# ESP_Grow_Main_Rev_A_2_3V_5V.net
KiCad netlist of a schematic drawn in Altium Designer
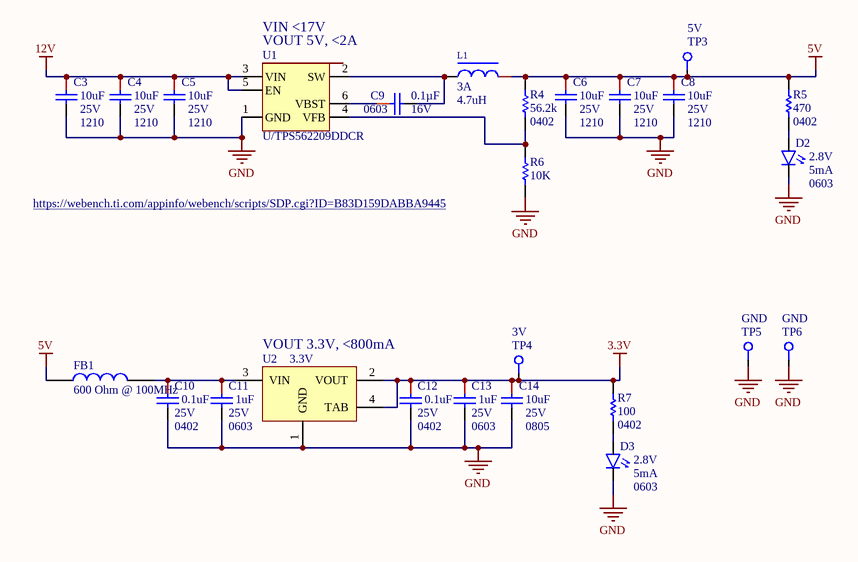
[diagram p0: ESP_Grow_Main_Rev_A_2_3V_5V.SchDoc]

(export (version "E")
  (design (tool "Eeschema 10.0.6"))
  (components
    (comp (ref "C3")
      (value "10uF")
      (footprint "CAPC1210(3225)_N")
      (description "10uF 1210 25V")
      (fields
        (field (name "MANUFACTURER") "TDK Corporation")
        (field (name "MANUFACTURER PART NUMBER") "C3225JB1E106K250AA")
        (field (name "PACKAGE / CASE") "1210")
        (field (name "VOLTAGE RATED") "25V")
      )
      (libsource (lib "OLogic-Passive") (part "CAP CER 10UF 25V JB 1210"))
    )
    (comp (ref "C4")
      (value "10uF")
      (footprint "CAPC1210(3225)_N")
      (description "10uF 1210 25V")
      (fields
        (field (name "MANUFACTURER") "TDK Corporation")
        (field (name "MANUFACTURER PART NUMBER") "C3225JB1E106K250AA")
        (field (name "PACKAGE / CASE") "1210")
        (field (name "VOLTAGE RATED") "25V")
      )
      (libsource (lib "OLogic-Passive") (part "CAP CER 10UF 25V JB 1210"))
    )
    (comp (ref "C5")
      (value "10uF")
      (footprint "CAPC1210(3225)_N")
      (description "10uF 1210 25V")
      (fields
        (field (name "MANUFACTURER") "TDK Corporation")
        (field (name "MANUFACTURER PART NUMBER") "C3225JB1E106K250AA")
        (field (name "PACKAGE / CASE") "1210")
        (field (name "VOLTAGE RATED") "25V")
      )
      (libsource (lib "OLogic-Passive") (part "CAP CER 10UF 25V JB 1210"))
    )
    (comp (ref "C6")
      (value "10uF")
      (footprint "CAPC1210(3225)_N")
      (description "10uF 1210 25V")
      (fields
        (field (name "MANUFACTURER") "TDK Corporation")
        (field (name "MANUFACTURER PART NUMBER") "C3225JB1E106K250AA")
        (field (name "PACKAGE / CASE") "1210")
        (field (name "VOLTAGE RATED") "25V")
      )
      (libsource (lib "OLogic-Passive") (part "CAP CER 10UF 25V JB 1210"))
    )
    (comp (ref "C7")
      (value "10uF")
      (footprint "CAPC1210(3225)_N")
      (description "10uF 1210 25V")
      (fields
        (field (name "MANUFACTURER") "TDK Corporation")
        (field (name "MANUFACTURER PART NUMBER") "C3225JB1E106K250AA")
        (field (name "PACKAGE / CASE") "1210")
        (field (name "VOLTAGE RATED") "25V")
      )
      (libsource (lib "OLogic-Passive") (part "CAP CER 10UF 25V JB 1210"))
    )
    (comp (ref "C8")
      (value "10uF")
      (footprint "CAPC1210(3225)_N")
      (description "10uF 1210 25V")
      (fields
        (field (name "MANUFACTURER") "TDK Corporation")
        (field (name "MANUFACTURER PART NUMBER") "C3225JB1E106K250AA")
        (field (name "PACKAGE / CASE") "1210")
        (field (name "VOLTAGE RATED") "25V")
      )
      (libsource (lib "OLogic-Passive") (part "CAP CER 10UF 25V JB 1210"))
    )
    (comp (ref "C9")
      (value "0.1uF")
      (footprint "CAPC0603(1608)_L")
      (description "0.1uF 0603 16V")
      (fields
        (field (name "MANUFACTURER") "Kemet")
        (field (name "MANUFACTURER PART NUMBER") "C0603C104K4RACTU")
        (field (name "CAPACITANCE") "0.1µF")
        (field (name "PACKAGE / CASE") "0603")
        (field (name "VOLTAGE - RATED") "16V")
      )
      (libsource (lib "OLogic-Passive") (part "CAP CER 0.1UF 16V 10% X7R 0603"))
    )
    (comp (ref "C10")
      (value "0.1uF")
      (footprint "CAPC0402(1005)_N")
      (description "0.1uF 0402 25V")
      (fields
        (field (name "MANUFACTURER") "Taiyo Yuden")
        (field (name "MANUFACTURER PART NUMBER") "TMK105BJ104KV-F")
        (field (name "PACKAGE / CASE") "0402")
        (field (name "VOLTAGE - RATED") "25V")
      )
      (libsource (lib "OLogic-Passive") (part "CAP CER 0.1UF 25V 10% X5R 0402"))
    )
    (comp (ref "C11")
      (value "1uF")
      (footprint "CAPC0603(1608)_N")
      (description "1uF 0603 25V")
      (fields
        (field (name "MANUFACTURER") "TDK Corporation")
        (field (name "MANUFACTURER PART NUMBER") "CGA3E1X7R1E105K080AC")
        (field (name "VOLTAGE - RATED") "25V")
        (field (name "PACKAGE / CASE") "0603")
      )
      (libsource (lib "OLogic-Passive") (part "CAP CER 1UF 25V 10% X7R 0603"))
    )
    (comp (ref "C12")
      (value "0.1uF")
      (footprint "CAPC0402(1005)_N")
      (description "0.1uF 0402 25V")
      (fields
        (field (name "MANUFACTURER") "Taiyo Yuden")
        (field (name "MANUFACTURER PART NUMBER") "TMK105BJ104KV-F")
        (field (name "PACKAGE / CASE") "0402")
        (field (name "VOLTAGE - RATED") "25V")
      )
      (libsource (lib "OLogic-Passive") (part "CAP CER 0.1UF 25V 10% X5R 0402"))
    )
    (comp (ref "C13")
      (value "1uF")
      (footprint "CAPC0603(1608)_N")
      (description "1uF 0603 25V")
      (fields
        (field (name "MANUFACTURER") "TDK Corporation")
        (field (name "MANUFACTURER PART NUMBER") "CGA3E1X7R1E105K080AC")
        (field (name "VOLTAGE - RATED") "25V")
        (field (name "PACKAGE / CASE") "0603")
      )
      (libsource (lib "OLogic-Passive") (part "CAP CER 1UF 25V 10% X7R 0603"))
    )
    (comp (ref "C14")
      (value "10uF")
      (footprint "CAPC0805(2012)_L")
      (description "10UF 25V X6R 0805")
      (fields
        (field (name "MANUFACTURER") "Murata Electronics North America")
        (field (name "MANUFACTURER PART NUMBER") "GRM21BC81E106ME51L")
        (field (name "VOLTAGE - RATED") "25V")
        (field (name "PACKAGE / CASE") "0805")
      )
      (libsource (lib "OLogic-Passive") (part "CAP CER 10UF 25V X6S 0805"))
    )
    (comp (ref "D2")
      (value "D/LEDB/0603")
      (footprint "D/0603")
      (fields
        (field (name "PACKAGE / CASE") "0603")
        (field (name "CURRENT - TEST") "5mA")
        (field (name "VOLTAGE - FORWARD (VF) (TYP)") "2.8V")
      )
      (libsource (lib "Kyle_Lib_04-20-19") (part "D/LEDB/0603"))
    )
    (comp (ref "D3")
      (value "D/LEDB/0603")
      (footprint "D/0603")
      (fields
        (field (name "PACKAGE / CASE") "0603")
        (field (name "CURRENT - TEST") "5mA")
        (field (name "VOLTAGE - FORWARD (VF) (TYP)") "2.8V")
      )
      (libsource (lib "Kyle_Lib_04-20-19") (part "D/LEDB/0603"))
    )
    (comp (ref "FB1")
      (value "600 Ohm @ 100MHz")
      (footprint "RESC0805(2012)_N")
      (description "600 OHM 0805 2.0A")
      (fields
        (field (name "MANUFACTURER") "Wurth Electronics Inc")
        (field (name "MANUFACTURER PART NUMBER") "742792040")
        (field (name "CREATOR") "osman")
      )
      (libsource (lib "OLogic-Passive") (part "FERRITE 600 OHM 2.0A 0805"))
    )
    (comp (ref "L1")
      (value "4.7uH")
      (footprint "INDP6060X45N")
      (description "FIXED IND 4.7UH 3A 37.6 MOHM SMD")
      (fields
        (field (name "MANUFACTURER PART NUMBER") "SRN6045-4R7Y")
        (field (name "CURRENT RATING (AMPS)") "3A")
        (field (name "INDUCTANCE") "4.7uH")
      )
      (libsource (lib "Kyle_Lib_04-20-19") (part "L/4.7uH/3A"))
    )
    (comp (ref "R4")
      (value "56.2K 1%")
      (footprint "RESC0402(1005)_N")
      (description "56.2K 1% 0402")
      (fields
        (field (name "MANUFACTURER") "Panasonic Electronic Components")
        (field (name "MANUFACTURER PART NUMBER") "ERJ-2RKF5622X")
        (field (name "RESISTANCE (OHMS)") "56.2k")
        (field (name "PACKAGE / CASE") "0402")
      )
      (libsource (lib "OLogic-Passive") (part "RES 56.2K OHM 1% 1/10W 0402"))
    )
    (comp (ref "R5")
      (value "470")
      (footprint "RESC0402(1005)_N")
      (description "470 0402")
      (fields
        (field (name "MANUFACTURER") "Panasonic Electronic Components")
        (field (name "MANUFACTURER PART NUMBER") "ERJ-2RKF4700X")
        (field (name "RESISTANCE (OHMS)") "470")
        (field (name "PACKAGE / CASE") "0402")
      )
      (libsource (lib "OLogic-Passive") (part "RES 470 OHM 1% 1/10W 0402"))
    )
    (comp (ref "R6")
      (value "10K")
      (footprint "RESC0402(1005)_N")
      (description "10K 0402")
      (fields
        (field (name "MANUFACTURER") "Samsung Electro-Mechanics")
        (field (name "MANUFACTURER PART NUMBER") "RC1005F103CS")
      )
      (libsource (lib "OLogic-Passive") (part "RES 10K OHM 1% 1/16W 0402"))
    )
    (comp (ref "R7")
      (value "100")
      (footprint "RESC0402(1005)_N")
      (description "100 0402")
      (fields
        (field (name "MANUFACTURER") "Yageo")
        (field (name "MANUFACTURER PART NUMBER") "RC0402FR-07100RL")
        (field (name "SUPPLIER DEVICE PACKAGE") "0402")
      )
      (libsource (lib "OLogic-Passive") (part "RES 100 OHM 1% 1/16W 0402"))
    )
    (comp (ref "TP3")
      (value "5V")
      (footprint "Pogo-Testpoint")
      (description "Test Point- Current one")
      (libsource (lib "OLogic Nexus Vault") (part "TestPoint"))
    )
    (comp (ref "TP4")
      (value "3V")
      (footprint "Pogo-Testpoint")
      (description "Test Point- Current one")
      (libsource (lib "OLogic Nexus Vault") (part "TestPoint"))
    )
    (comp (ref "TP5")
      (value "GND")
      (footprint "Pogo-Testpoint")
      (description "Test Point- Current one")
      (libsource (lib "OLogic Nexus Vault") (part "TestPoint"))
    )
    (comp (ref "TP6")
      (value "GND")
      (footprint "Pogo-Testpoint")
      (description "Test Point- Current one")
      (libsource (lib "OLogic Nexus Vault") (part "TestPoint"))
    )
    (comp (ref "U1")
      (value "U/TPS562209DDCR")
      (footprint "SOT-23")
      (description "IC REG BUCK ADJ 2A TSOT23-6")
      (fields (field (name "MANUFACTURER PART NUMBER") "TPS562209DDCR"))
      (libsource (lib "Kyle_Lib_04-20-19") (part "U/TPS562209DDCR"))
    )
    (comp (ref "U2")
      (value "3.3V")
      (footprint "DSO-G3")
      (description "3.3 volt fixed regulator, 800mA")
      (libsource (lib "OLogic-Reg-Convert") (part "LD1117S33"))
    )
  )
  (nets
    (net (code "1") (name "3.3V") (class "Default")
      (node (ref "C12") (pin "1") (pinfunction "1_1") (pintype "passive"))
      (node (ref "C13") (pin "1") (pinfunction "1_1") (pintype "passive"))
      (node (ref "C14") (pin "1") (pinfunction "1_1") (pintype "passive"))
      (node (ref "R7") (pin "2") (pinfunction "2_2") (pintype "passive"))
      (node (ref "TP4") (pin "1") (pinfunction "1_1") (pintype "passive"))
      (node (ref "U2") (pin "2") (pinfunction "VOUT_2") (pintype "power_in"))
      (node (ref "U2") (pin "4") (pinfunction "TAB_4") (pintype "power_in"))
    )
    (net (code "2") (name "5V") (class "Default")
      (node (ref "C6") (pin "1") (pinfunction "1_1") (pintype "passive"))
      (node (ref "C7") (pin "1") (pinfunction "1_1") (pintype "passive"))
      (node (ref "C8") (pin "1") (pinfunction "1_1") (pintype "passive"))
      (node (ref "FB1") (pin "1") (pinfunction "1_1") (pintype "passive"))
      (node (ref "L1") (pin "1") (pinfunction "1_1") (pintype "power_in"))
      (node (ref "R4") (pin "2") (pinfunction "2_2") (pintype "passive"))
      (node (ref "R5") (pin "2") (pinfunction "2_2") (pintype "passive"))
      (node (ref "TP3") (pin "1") (pinfunction "1_1") (pintype "passive"))
    )
    (net (code "3") (name "12V") (class "Default")
      (node (ref "C3") (pin "1") (pinfunction "1_1") (pintype "passive"))
      (node (ref "C4") (pin "1") (pinfunction "1_1") (pintype "passive"))
      (node (ref "C5") (pin "1") (pinfunction "1_1") (pintype "passive"))
      (node (ref "U1") (pin "3") (pinfunction "VIN_3") (pintype "power_in"))
      (node (ref "U1") (pin "5") (pinfunction "EN_5") (pintype "power_in"))
    )
    (net (code "4") (name "GND") (class "Default")
      (node (ref "C10") (pin "2") (pinfunction "2_2") (pintype "passive"))
      (node (ref "C11") (pin "2") (pinfunction "2_2") (pintype "passive"))
      (node (ref "C12") (pin "2") (pinfunction "2_2") (pintype "passive"))
      (node (ref "C13") (pin "2") (pinfunction "2_2") (pintype "passive"))
      (node (ref "C14") (pin "2") (pinfunction "2_2") (pintype "passive"))
      (node (ref "C3") (pin "2") (pinfunction "2_2") (pintype "passive"))
      (node (ref "C4") (pin "2") (pinfunction "2_2") (pintype "passive"))
      (node (ref "C5") (pin "2") (pinfunction "2_2") (pintype "passive"))
      (node (ref "C6") (pin "2") (pinfunction "2_2") (pintype "passive"))
      (node (ref "C7") (pin "2") (pinfunction "2_2") (pintype "passive"))
      (node (ref "C8") (pin "2") (pinfunction "2_2") (pintype "passive"))
      (node (ref "D2") (pin "1") (pinfunction "1_1") (pintype "passive"))
      (node (ref "D3") (pin "1") (pinfunction "1_1") (pintype "passive"))
      (node (ref "R6") (pin "1") (pinfunction "1_1") (pintype "passive"))
      (node (ref "TP5") (pin "1") (pinfunction "1_1") (pintype "passive"))
      (node (ref "TP6") (pin "1") (pinfunction "1_1") (pintype "passive"))
      (node (ref "U1") (pin "1") (pinfunction "GND_1") (pintype "power_in"))
      (node (ref "U2") (pin "1") (pinfunction "GND_1") (pintype "power_in"))
    )
    (net (code "5") (name "Net-(D2-Pad2)") (class "Default")
      (node (ref "D2") (pin "2") (pinfunction "2_2") (pintype "passive"))
      (node (ref "R5") (pin "1") (pinfunction "1_1") (pintype "passive"))
    )
    (net (code "6") (name "Net-(D3-Pad2)") (class "Default")
      (node (ref "D3") (pin "2") (pinfunction "2_2") (pintype "passive"))
      (node (ref "R7") (pin "1") (pinfunction "1_1") (pintype "passive"))
    )
    (net (code "7") (name "Net-(U1-SW)") (class "Default")
      (node (ref "C9") (pin "2") (pinfunction "2_2") (pintype "passive"))
      (node (ref "L1") (pin "2") (pinfunction "2_2") (pintype "power_in"))
      (node (ref "U1") (pin "2") (pinfunction "SW_2") (pintype "power_in"))
    )
    (net (code "8") (name "Net-(U1-VBST)") (class "Default")
      (node (ref "C9") (pin "1") (pinfunction "1_1") (pintype "passive"))
      (node (ref "U1") (pin "6") (pinfunction "VBST_6") (pintype "power_in"))
    )
    (net (code "9") (name "Net-(U1-VFB)") (class "Default")
      (node (ref "R4") (pin "1") (pinfunction "1_1") (pintype "passive"))
      (node (ref "R6") (pin "2") (pinfunction "2_2") (pintype "passive"))
      (node (ref "U1") (pin "4") (pinfunction "VFB_4") (pintype "power_in"))
    )
    (net (code "10") (name "Net-(U2-VIN)") (class "Default")
      (node (ref "C10") (pin "1") (pinfunction "1_1") (pintype "passive"))
      (node (ref "C11") (pin "1") (pinfunction "1_1") (pintype "passive"))
      (node (ref "FB1") (pin "2") (pinfunction "2_2") (pintype "passive"))
      (node (ref "U2") (pin "3") (pinfunction "VIN_3") (pintype "power_in"))
    )
  )
)
